# Sheet1.net
KiCad netlist of a schematic drawn in Altium Designer
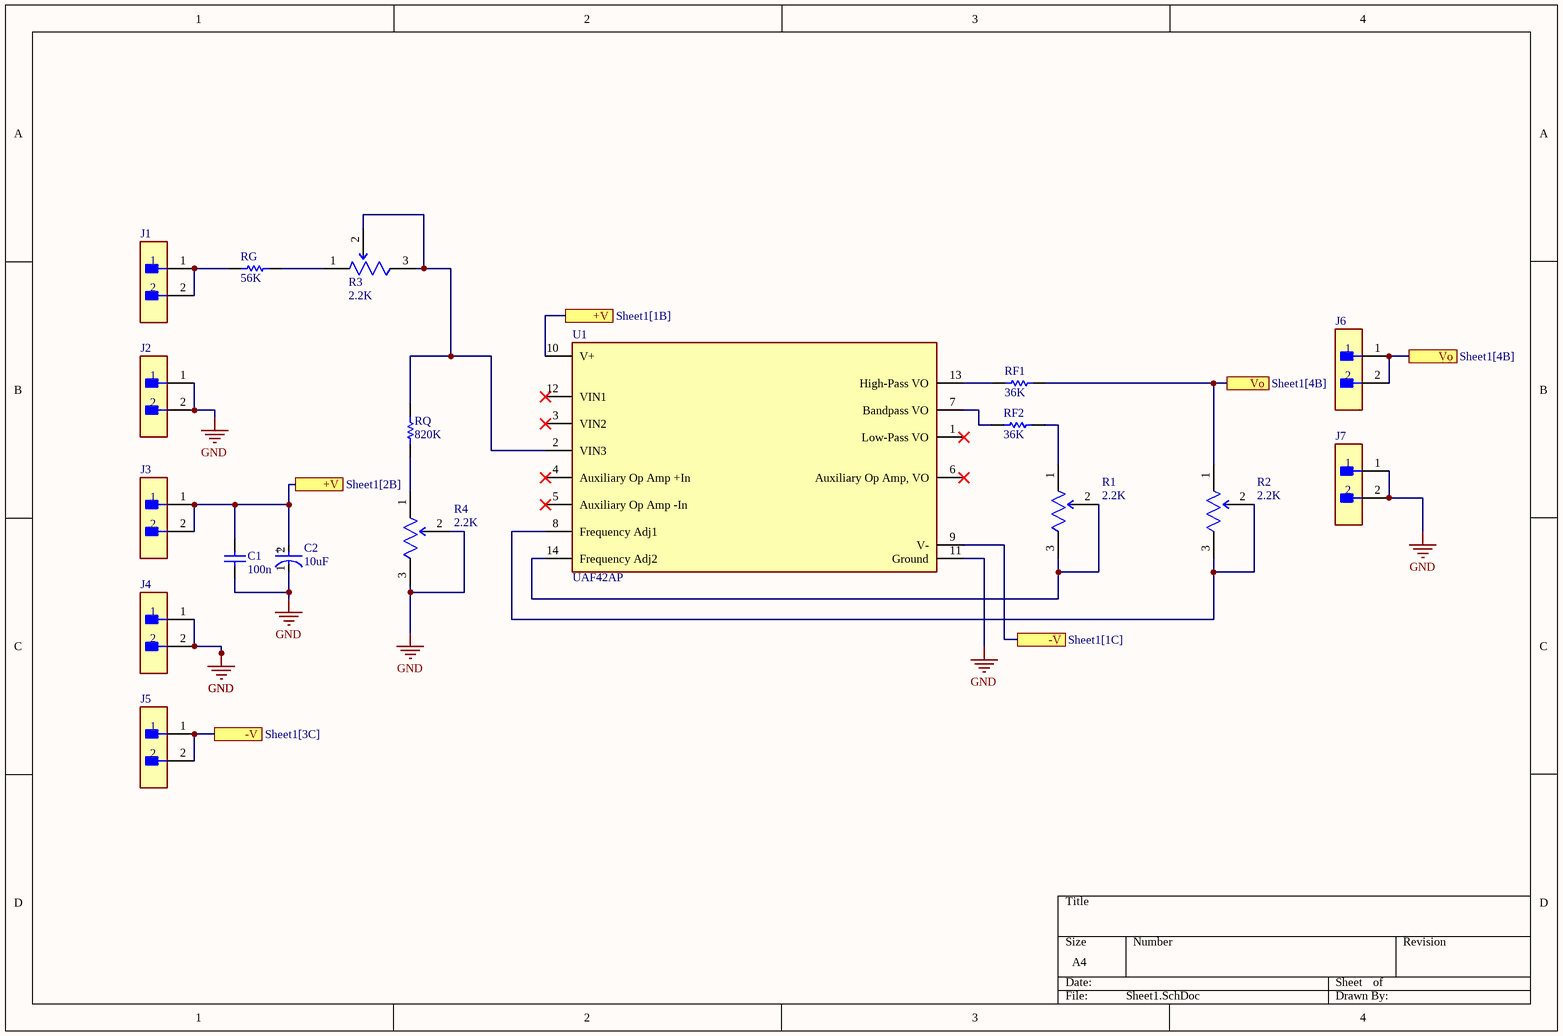
[diagram p0: Sheet1.SchDoc]

(export (version "E")
  (design (tool "Eeschema 10.0.6"))
  (components
    (comp (ref "C1")
      (value "100n")
      (description "Capacitor")
      (libsource (lib "Simulation Generic Components") (part "Capacitor"))
    )
    (comp (ref "C2")
      (value "10uF")
      (footprint "FP-RAD-TH-D_5_0_5-L_11_1-MFG")
      (description "Aluminum Electrolytic Capacitors (Radial Lead Type) AEC-Q200 Qualified 10uF ±20% 50V")
      (fields (field (name "TOLERANCE") "20%"))
      (libsource (lib "Altium Content Vault") (part "a00bbbee19879c290e62620ae7e47b1"))
    )
    (comp (ref "J1")
      (value "M20-9990246")
      (footprint "FP-M20-9990246-MFG")
      (description "CONN HEADER VERT 2POS 2.54MM")
      (fields
        (field (name "OCTOPART") "https://octopart.com/m20-9990246-harwin-2590635")
        (field (name "MANUFACTURER") "Harwin")
      )
      (libsource (lib "Altium Content Vault") (part "3bc925449376181038e59eaffc5286c"))
    )
    (comp (ref "J2")
      (value "M20-9990246")
      (footprint "FP-M20-9990246-MFG")
      (description "CONN HEADER VERT 2POS 2.54MM")
      (fields
        (field (name "OCTOPART") "https://octopart.com/m20-9990246-harwin-2590635")
        (field (name "MANUFACTURER") "Harwin")
      )
      (libsource (lib "Altium Content Vault") (part "3bc925449376181038e59eaffc5286c"))
    )
    (comp (ref "J3")
      (value "M20-9990246")
      (footprint "FP-M20-9990246-MFG")
      (description "CONN HEADER VERT 2POS 2.54MM")
      (fields
        (field (name "OCTOPART") "https://octopart.com/m20-9990246-harwin-2590635")
        (field (name "MANUFACTURER") "Harwin")
      )
      (libsource (lib "Altium Content Vault") (part "3bc925449376181038e59eaffc5286c"))
    )
    (comp (ref "J4")
      (value "M20-9990246")
      (footprint "FP-M20-9990246-MFG")
      (description "CONN HEADER VERT 2POS 2.54MM")
      (fields
        (field (name "OCTOPART") "https://octopart.com/m20-9990246-harwin-2590635")
        (field (name "MANUFACTURER") "Harwin")
      )
      (libsource (lib "Altium Content Vault") (part "3bc925449376181038e59eaffc5286c"))
    )
    (comp (ref "J5")
      (value "M20-9990246")
      (footprint "FP-M20-9990246-MFG")
      (description "CONN HEADER VERT 2POS 2.54MM")
      (fields
        (field (name "OCTOPART") "https://octopart.com/m20-9990246-harwin-2590635")
        (field (name "MANUFACTURER") "Harwin")
      )
      (libsource (lib "Altium Content Vault") (part "3bc925449376181038e59eaffc5286c"))
    )
    (comp (ref "J6")
      (value "M20-9990246")
      (footprint "FP-M20-9990246-MFG")
      (description "CONN HEADER VERT 2POS 2.54MM")
      (fields
        (field (name "OCTOPART") "https://octopart.com/m20-9990246-harwin-2590635")
        (field (name "MANUFACTURER") "Harwin")
      )
      (libsource (lib "Altium Content Vault") (part "3bc925449376181038e59eaffc5286c"))
    )
    (comp (ref "J7")
      (value "M20-9990246")
      (footprint "FP-M20-9990246-MFG")
      (description "CONN HEADER VERT 2POS 2.54MM")
      (fields
        (field (name "OCTOPART") "https://octopart.com/m20-9990246-harwin-2590635")
        (field (name "MANUFACTURER") "Harwin")
      )
      (libsource (lib "Altium Content Vault") (part "3bc925449376181038e59eaffc5286c"))
    )
    (comp (ref "R1")
      (value "2.2K")
      (footprint "FP-3296W-MFG")
      (description "TRIMMER 10K OHM 0.5W PC PIN TOP")
      (fields (field (name "TOLERANCE") "10%"))
      (libsource (lib "Altium Content Vault") (part "194907ebf2981c0cdd5d9631a0af656"))
    )
    (comp (ref "R2")
      (value "2.2K")
      (footprint "FP-3296W-MFG")
      (description "TRIMMER 10K OHM 0.5W PC PIN TOP")
      (fields (field (name "TOLERANCE") "10%"))
      (libsource (lib "Altium Content Vault") (part "194907ebf2981c0cdd5d9631a0af656"))
    )
    (comp (ref "R3")
      (value "2.2K")
      (footprint "FP-3296W-MFG")
      (description "TRIMMER 10K OHM 0.5W PC PIN TOP")
      (fields (field (name "TOLERANCE") "10%"))
      (libsource (lib "Altium Content Vault") (part "194907ebf2981c0cdd5d9631a0af656"))
    )
    (comp (ref "R4")
      (value "2.2K")
      (footprint "FP-3296W-MFG")
      (description "TRIMMER 10K OHM 0.5W PC PIN TOP")
      (fields (field (name "TOLERANCE") "10%"))
      (libsource (lib "Altium Content Vault") (part "194907ebf2981c0cdd5d9631a0af656"))
    )
    (comp (ref "RF1")
      (value "36K")
      (description "Resistor")
      (libsource (lib "Simulation Generic Components") (part "Resistor"))
    )
    (comp (ref "RF2")
      (value "36K")
      (description "Resistor")
      (libsource (lib "Simulation Generic Components") (part "Resistor"))
    )
    (comp (ref "RG")
      (value "56K")
      (description "Resistor")
      (libsource (lib "Simulation Generic Components") (part "Resistor"))
    )
    (comp (ref "RQ")
      (value "820K")
      (description "Resistor")
      (libsource (lib "Simulation Generic Components") (part "Resistor"))
    )
    (comp (ref "U1")
      (value "UAF42AP")
      (footprint "FP-N0014A-MFG")
      (description "IC FILTER 100KHZ UNIV 14DIP")
      (libsource (lib "Altium Content Vault") (part "4501753ccc0aa72ddbce73a84f5efd1"))
    )
  )
  (nets
    (net (code "1") (name "/+V") (class "Default")
      (node (ref "C1") (pin "2") (pinfunction "2_2") (pintype "passive"))
      (node (ref "C2") (pin "2") (pinfunction "A_2") (pintype "passive"))
      (node (ref "J3") (pin "1") (pinfunction "1_1") (pintype "passive"))
      (node (ref "J3") (pin "2") (pinfunction "2_2") (pintype "passive"))
      (node (ref "U1") (pin "10") (pinfunction "V+_10") (pintype "power_in"))
    )
    (net (code "2") (name "/-V") (class "Default")
      (node (ref "J5") (pin "1") (pinfunction "1_1") (pintype "passive"))
      (node (ref "J5") (pin "2") (pinfunction "2_2") (pintype "passive"))
      (node (ref "U1") (pin "9") (pinfunction "V-_9") (pintype "power_in"))
    )
    (net (code "3") (name "/Vo") (class "Default")
      (node (ref "J6") (pin "1") (pinfunction "1_1") (pintype "passive"))
      (node (ref "J6") (pin "2") (pinfunction "2_2") (pintype "passive"))
      (node (ref "R2") (pin "1") (pinfunction "CCW_1") (pintype "passive"))
      (node (ref "RF1") (pin "2") (pinfunction "2_2") (pintype "passive"))
    )
    (net (code "4") (name "GND") (class "Default")
      (node (ref "C1") (pin "1") (pinfunction "1_1") (pintype "passive"))
      (node (ref "C2") (pin "1") (pinfunction "C_1") (pintype "passive"))
      (node (ref "J2") (pin "1") (pinfunction "1_1") (pintype "passive"))
      (node (ref "J2") (pin "2") (pinfunction "2_2") (pintype "passive"))
      (node (ref "J4") (pin "1") (pinfunction "1_1") (pintype "passive"))
      (node (ref "J4") (pin "2") (pinfunction "2_2") (pintype "passive"))
      (node (ref "J7") (pin "1") (pinfunction "1_1") (pintype "passive"))
      (node (ref "J7") (pin "2") (pinfunction "2_2") (pintype "passive"))
      (node (ref "R4") (pin "2") (pinfunction "WIPER_2") (pintype "passive"))
      (node (ref "R4") (pin "3") (pinfunction "CW_3") (pintype "passive"))
      (node (ref "U1") (pin "11") (pinfunction "Ground_11") (pintype "power_in"))
    )
    (net (code "5") (name "Net-(J1-Pad1)") (class "Default")
      (node (ref "J1") (pin "1") (pinfunction "1_1") (pintype "passive"))
      (node (ref "J1") (pin "2") (pinfunction "2_2") (pintype "passive"))
      (node (ref "RG") (pin "1") (pinfunction "1_1") (pintype "passive"))
    )
    (net (code "6") (name "Net-(R1-CCW)") (class "Default")
      (node (ref "R1") (pin "1") (pinfunction "CCW_1") (pintype "passive"))
      (node (ref "RF2") (pin "2") (pinfunction "2_2") (pintype "passive"))
    )
    (net (code "7") (name "Net-(R1-CW)") (class "Default")
      (node (ref "R1") (pin "2") (pinfunction "WIPER_2") (pintype "passive"))
      (node (ref "R1") (pin "3") (pinfunction "CW_3") (pintype "passive"))
      (node (ref "U1") (pin "14") (pinfunction "Frequency_Adj2_14") (pintype "passive"))
    )
    (net (code "8") (name "Net-(R2-CW)") (class "Default")
      (node (ref "R2") (pin "2") (pinfunction "WIPER_2") (pintype "passive"))
      (node (ref "R2") (pin "3") (pinfunction "CW_3") (pintype "passive"))
      (node (ref "U1") (pin "8") (pinfunction "Frequency_Adj1_8") (pintype "passive"))
    )
    (net (code "9") (name "Net-(R3-CCW)") (class "Default")
      (node (ref "R3") (pin "1") (pinfunction "CCW_1") (pintype "passive"))
      (node (ref "RG") (pin "2") (pinfunction "2_2") (pintype "passive"))
    )
    (net (code "10") (name "Net-(R3-CW)") (class "Default")
      (node (ref "R3") (pin "2") (pinfunction "WIPER_2") (pintype "passive"))
      (node (ref "R3") (pin "3") (pinfunction "CW_3") (pintype "passive"))
      (node (ref "RQ") (pin "2") (pinfunction "2_2") (pintype "passive"))
      (node (ref "U1") (pin "2") (pinfunction "VIN3_2") (pintype "passive"))
    )
    (net (code "11") (name "Net-(R4-CCW)") (class "Default")
      (node (ref "R4") (pin "1") (pinfunction "CCW_1") (pintype "passive"))
      (node (ref "RQ") (pin "1") (pinfunction "1_1") (pintype "passive"))
    )
    (net (code "12") (name "Net-(U1-Bandpass_VO)") (class "Default")
      (node (ref "RF2") (pin "1") (pinfunction "1_1") (pintype "passive"))
      (node (ref "U1") (pin "7") (pinfunction "Bandpass_VO_7") (pintype "passive"))
    )
    (net (code "13") (name "Net-(U1-High-Pass_VO)") (class "Default")
      (node (ref "RF1") (pin "1") (pinfunction "1_1") (pintype "passive"))
      (node (ref "U1") (pin "13") (pinfunction "High-Pass_VO_13") (pintype "passive"))
    )
    (net (code "14") (name "unconnected-(U1-Auxiliary_Op_Amp,_VO-Pad6)") (class "Default")
      (node (ref "U1") (pin "6") (pinfunction "Auxiliary_Op_Amp,_VO_6") (pintype "passive+no_connect"))
    )
    (net (code "15") (name "unconnected-(U1-Auxiliary_Op_Amp_+In-Pad4)") (class "Default")
      (node (ref "U1") (pin "4") (pinfunction "Auxiliary_Op_Amp_+In_4") (pintype "passive+no_connect"))
    )
    (net (code "16") (name "unconnected-(U1-Auxiliary_Op_Amp_-In-Pad5)") (class "Default")
      (node (ref "U1") (pin "5") (pinfunction "Auxiliary_Op_Amp_-In_5") (pintype "passive+no_connect"))
    )
    (net (code "17") (name "unconnected-(U1-Low-Pass_VO-Pad1)") (class "Default")
      (node (ref "U1") (pin "1") (pinfunction "Low-Pass_VO_1") (pintype "passive+no_connect"))
    )
    (net (code "18") (name "unconnected-(U1-VIN1-Pad12)") (class "Default")
      (node (ref "U1") (pin "12") (pinfunction "VIN1_12") (pintype "passive+no_connect"))
    )
    (net (code "19") (name "unconnected-(U1-VIN2-Pad3)") (class "Default")
      (node (ref "U1") (pin "3") (pinfunction "VIN2_3") (pintype "passive+no_connect"))
    )
  )
)
